# LEDMiniCube_Main.net
KiCad netlist of a schematic drawn in Altium Designer
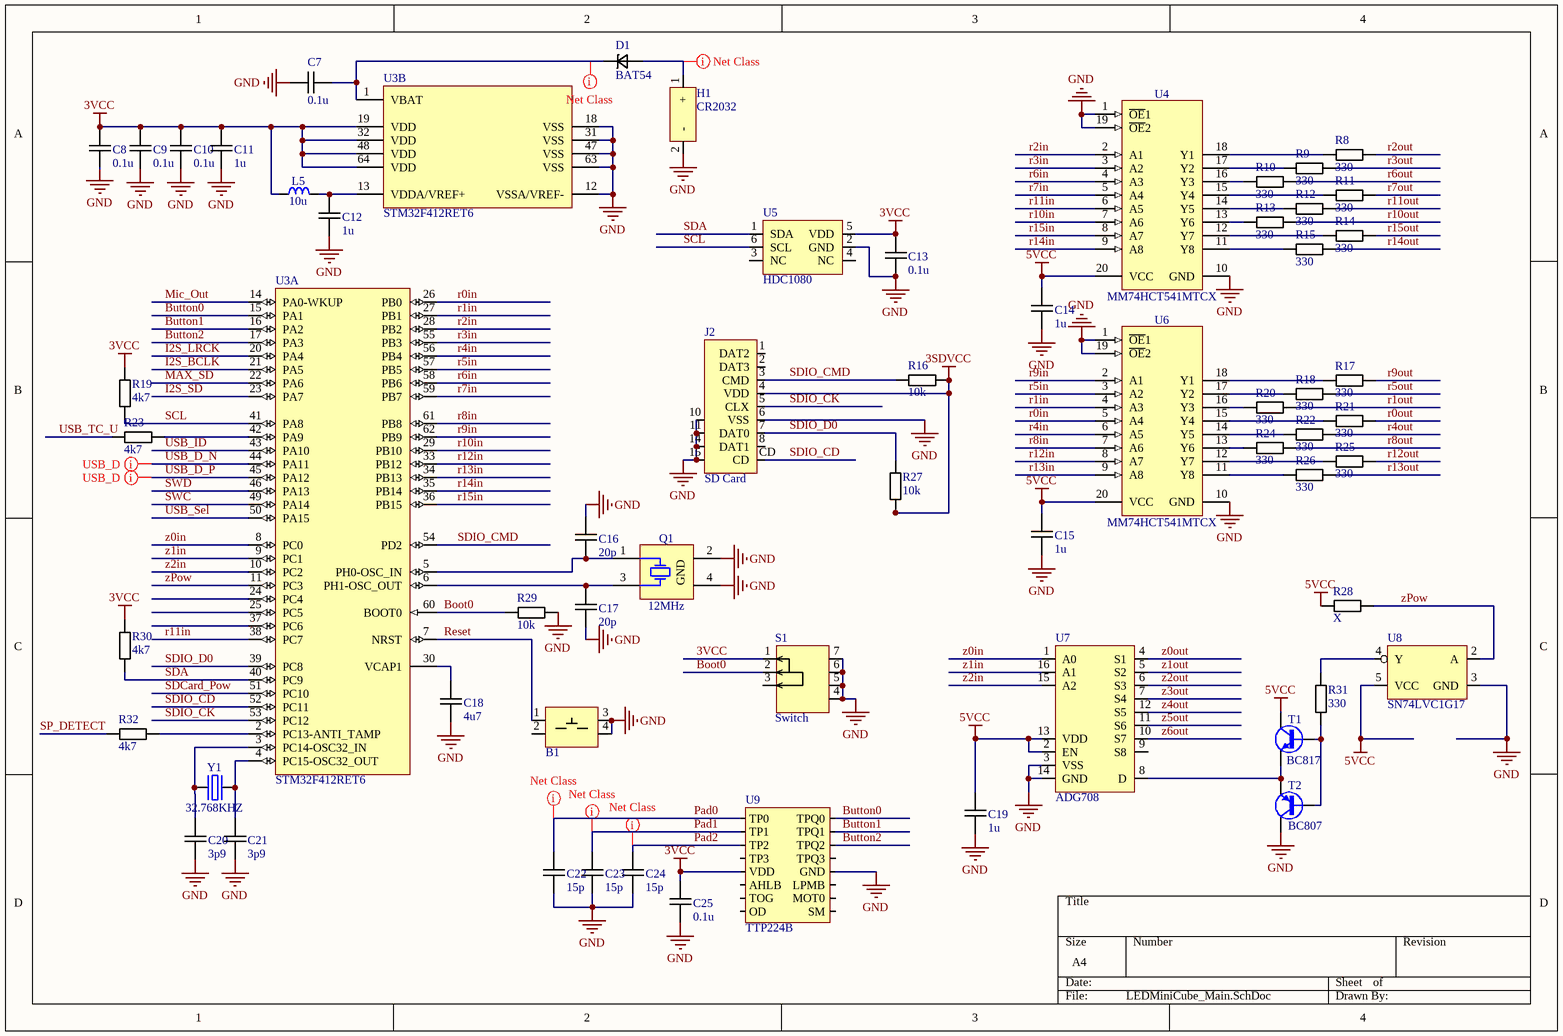
[diagram p0: LEDMiniCube_Main.SchDoc]

(export (version "E")
  (design (tool "Eeschema 10.0.6"))
  (components
    (comp (ref "B1")
      (value "Button 5.2")
      (footprint "Button 5.2x5.2")
      (libsource (lib "BMFT_lib") (part "Button 5.2"))
    )
    (comp (ref "C7") (value "0.1u") (footprint "CAPC1608L") (libsource (lib "BMFT_lib") (part "Capacitor")))
    (comp (ref "C8") (value "0.1u") (footprint "CAPC1608L") (libsource (lib "BMFT_lib") (part "Capacitor")))
    (comp (ref "C9") (value "0.1u") (footprint "CAPC1608L") (libsource (lib "BMFT_lib") (part "Capacitor")))
    (comp (ref "C10") (value "0.1u") (footprint "CAPC1608L") (libsource (lib "BMFT_lib") (part "Capacitor")))
    (comp (ref "C11") (value "1u") (footprint "CAPC1608L") (libsource (lib "BMFT_lib") (part "Capacitor")))
    (comp (ref "C12") (value "1u") (footprint "CAPC1608L") (libsource (lib "BMFT_lib") (part "Capacitor")))
    (comp (ref "C13") (value "0.1u") (footprint "CAPC1608L") (libsource (lib "BMFT_lib") (part "Capacitor")))
    (comp (ref "C14") (value "1u") (footprint "CAPC2012L") (libsource (lib "BMFT_lib") (part "Capacitor")))
    (comp (ref "C15") (value "1u") (footprint "CAPC2012L") (libsource (lib "BMFT_lib") (part "Capacitor")))
    (comp (ref "C16") (value "20p") (footprint "CAPC1608L") (libsource (lib "BMFT_lib") (part "Capacitor")))
    (comp (ref "C17") (value "20p") (footprint "CAPC1608L") (libsource (lib "BMFT_lib") (part "Capacitor")))
    (comp (ref "C18") (value "4u7") (footprint "CAPC2012L") (libsource (lib "BMFT_lib") (part "Capacitor")))
    (comp (ref "C19") (value "1u") (footprint "CAPC2012L") (libsource (lib "BMFT_lib") (part "Capacitor")))
    (comp (ref "C20") (value "3p9") (footprint "CAPC1608L") (libsource (lib "BMFT_lib") (part "Capacitor")))
    (comp (ref "C21") (value "3p9") (footprint "CAPC1608L") (libsource (lib "BMFT_lib") (part "Capacitor")))
    (comp (ref "C22") (value "15p") (footprint "CAPC1608L") (libsource (lib "BMFT_lib") (part "Capacitor")))
    (comp (ref "C23") (value "15p") (footprint "CAPC1608L") (libsource (lib "BMFT_lib") (part "Capacitor")))
    (comp (ref "C24") (value "15p") (footprint "CAPC1608L") (libsource (lib "BMFT_lib") (part "Capacitor")))
    (comp (ref "C25") (value "0.1u") (footprint "CAPC1608L") (libsource (lib "BMFT_lib") (part "Capacitor")))
    (comp (ref "D1") (value "BAT54") (footprint "SOD-323F") (libsource (lib "BMFT_lib") (part "Schotky")))
    (comp (ref "H1")
      (value "CR2032")
      (footprint "Battery Holder cr2032")
      (libsource (lib "BMFT_lib") (part "CR2032"))
    )
    (comp (ref "J2")
      (value "SD Card")
      (footprint "XUNPU TF-115")
      (libsource (lib "BMFT_lib") (part "SD Card Socket"))
    )
    (comp (ref "L5")
      (value "10u")
      (footprint "IND_ABRACON_AISC-0603")
      (description "Inductor")
      (fields (field (name "AUTHOR") "CERN DEM JLC"))
      (libsource (lib "Inductors & Transformers") (part "Inductor"))
    )
    (comp (ref "Q1")
      (value "12MHz")
      (footprint "XTAL_TXC_7M")
      (description "Crystal 4 pins 1=XTAL Control 2=GND3=XTAL 4=GND")
      (fields
        (field (name "PART NUMBER") "XTAL_12MHZ_TXC_7M-12.000MAAJ-T")
        (field (name "MANUFACTURER") "TXC CORPORATION")
        (field (name "AUTHOR") "CERN DEM JLC")
      )
      (libsource (lib "ICs And Semiconductors") (part "Quartz Crystal 1X 2GND 3X 4GND"))
    )
    (comp (ref "R8") (value "330") (footprint "RESC2012L") (libsource (lib "BMFT_lib") (part "Resistor")))
    (comp (ref "R9") (value "330") (footprint "RESC2012L") (libsource (lib "BMFT_lib") (part "Resistor")))
    (comp (ref "R10") (value "330") (footprint "RESC2012L") (libsource (lib "BMFT_lib") (part "Resistor")))
    (comp (ref "R11") (value "330") (footprint "RESC2012L") (libsource (lib "BMFT_lib") (part "Resistor")))
    (comp (ref "R12") (value "330") (footprint "RESC2012L") (libsource (lib "BMFT_lib") (part "Resistor")))
    (comp (ref "R13") (value "330") (footprint "RESC2012L") (libsource (lib "BMFT_lib") (part "Resistor")))
    (comp (ref "R14") (value "330") (footprint "RESC2012L") (libsource (lib "BMFT_lib") (part "Resistor")))
    (comp (ref "R15") (value "330") (footprint "RESC2012L") (libsource (lib "BMFT_lib") (part "Resistor")))
    (comp (ref "R16") (value "10k") (footprint "RESC1608L") (libsource (lib "BMFT_lib") (part "Resistor")))
    (comp (ref "R17") (value "330") (footprint "RESC2012L") (libsource (lib "BMFT_lib") (part "Resistor")))
    (comp (ref "R18") (value "330") (footprint "RESC2012L") (libsource (lib "BMFT_lib") (part "Resistor")))
    (comp (ref "R19") (value "4k7") (footprint "RESC1608L") (libsource (lib "BMFT_lib") (part "Resistor")))
    (comp (ref "R20") (value "330") (footprint "RESC2012L") (libsource (lib "BMFT_lib") (part "Resistor")))
    (comp (ref "R21") (value "330") (footprint "RESC2012L") (libsource (lib "BMFT_lib") (part "Resistor")))
    (comp (ref "R22") (value "330") (footprint "RESC2012L") (libsource (lib "BMFT_lib") (part "Resistor")))
    (comp (ref "R23") (value "4k7") (footprint "RESC1608L") (libsource (lib "BMFT_lib") (part "Resistor")))
    (comp (ref "R24") (value "330") (footprint "RESC2012L") (libsource (lib "BMFT_lib") (part "Resistor")))
    (comp (ref "R25") (value "330") (footprint "RESC2012L") (libsource (lib "BMFT_lib") (part "Resistor")))
    (comp (ref "R26") (value "330") (footprint "RESC2012L") (libsource (lib "BMFT_lib") (part "Resistor")))
    (comp (ref "R27") (value "10k") (footprint "RESC1608L") (libsource (lib "BMFT_lib") (part "Resistor")))
    (comp (ref "R28") (value "X") (footprint "RESC1608L") (libsource (lib "BMFT_lib") (part "Resistor")))
    (comp (ref "R29") (value "10k") (footprint "RESC1608L") (libsource (lib "BMFT_lib") (part "Resistor")))
    (comp (ref "R30") (value "4k7") (footprint "RESC1608L") (libsource (lib "BMFT_lib") (part "Resistor")))
    (comp (ref "R31") (value "330") (footprint "RESC1608L") (libsource (lib "BMFT_lib") (part "Resistor")))
    (comp (ref "R32") (value "4k7") (footprint "RESC1608L") (libsource (lib "BMFT_lib") (part "Resistor")))
    (comp (ref "S1") (value "Switch") (footprint "TA-3524A-A1") (libsource (lib "BMFT_lib") (part "Switch")))
    (comp (ref "T1")
      (value "BC817")
      (footprint "SOT95P230X110-3N")
      (description "NPN Transistor")
      (fields (field (name "PART NUMBER") "BC817-40") (field (name "AUTHOR") "CERN DEM JLC"))
      (libsource (lib "ICs And Semiconductors") (part "NPN B1 E2 C3"))
    )
    (comp (ref "T2")
      (value "BC807")
      (footprint "SOT95P230X110-3N")
      (description "PNP Transistor")
      (fields (field (name "PART NUMBER") "BC807-40") (field (name "AUTHOR") "CERN DEM JLC"))
      (libsource (lib "ICs And Semiconductors") (part "PNP B1 E2 C3"))
    )
    (comp (ref "U3")
      (value "STM32F412RET6")
      (footprint "STM-LQFP64_N")
      (libsource (lib "STMicroelectronics STM32 F4") (part "STM32F401RBT6"))
    )
    (comp (ref "U4")
      (value "MM74HCT541MTCX")
      (footprint "TSOP65P640X120-20N")
      (description "Octal Buffer/Line Driver with 3-State Outputs")
      (libsource (lib "Standard Logic") (part "74541"))
    )
    (comp (ref "U5")
      (value "HDC1080")
      (footprint "WSON HDC1080")
      (libsource (lib "BMFT_lib") (part "HDC1080"))
    )
    (comp (ref "U6")
      (value "MM74HCT541MTCX")
      (footprint "TSOP65P640X120-20N")
      (description "Octal Buffer/Line Driver with 3-State Outputs")
      (libsource (lib "Standard Logic") (part "74541"))
    )
    (comp (ref "U7")
      (value "ADG708")
      (footprint "TSOP65P640X110-16N")
      (fields (field (name "PART") "ADG708BRUZ"))
      (libsource (lib "BMFT_lib") (part "ADG708"))
    )
    (comp (ref "U8")
      (value "SN74LVC1G17")
      (footprint "SOT23-5AL")
      (fields (field (name "PART") "SN74LVC1G17DBVR"))
      (libsource (lib "BMFT_lib") (part "SN74LVC1G04"))
    )
    (comp (ref "U9")
      (value "TTP224B")
      (footprint "SOP65P640-16L")
      (libsource (lib "BMFT_lib") (part "TTP224"))
    )
    (comp (ref "Y1")
      (value "32.768KHZ")
      (footprint "XTAL_ABRACON_ABS09")
      (description "Quartz Crystal")
      (fields
        (field (name "PART NUMBER") "XTAL_32.768KHZ_ABRACON_ABS09-32.768KHZ-T")
        (field (name "MANUFACTURER") "ABRACON")
        (field (name "AUTHOR") "CERN DEM JLC")
      )
      (libsource (lib "ICs And Semiconductors") (part "Quartz Crystal"))
    )
  )
  (nets
    (net (code "1") (name "/Boot0") (class "Default")
      (node (ref "R29") (pin "1") (pintype "passive"))
      (node (ref "S1") (pin "2") (pinfunction "2_2") (pintype "passive"))
      (node (ref "U3") (pin "60") (pinfunction "BOOT0_60") (pintype "input"))
    )
    (net (code "2") (name "/Button0") (class "Default")
      (node (ref "U3") (pin "15") (pinfunction "PA1_15") (pintype "bidirectional"))
      (node (ref "U9") (pin "16") (pinfunction "TPQ0_16") (pintype "passive"))
    )
    (net (code "3") (name "/Button1") (class "Default")
      (node (ref "U3") (pin "16") (pinfunction "PA2_16") (pintype "bidirectional"))
      (node (ref "U9") (pin "15") (pinfunction "TPQ1_15") (pintype "passive"))
    )
    (net (code "4") (name "/Button2") (class "Default")
      (node (ref "U3") (pin "17") (pinfunction "PA3_17") (pintype "bidirectional"))
      (node (ref "U9") (pin "14") (pinfunction "TPQ2_14") (pintype "passive"))
    )
    (net (code "5") (name "/I2S_BCLK") (class "Default")
      (node (ref "U3") (pin "21") (pinfunction "PA5_21") (pintype "bidirectional"))
    )
    (net (code "6") (name "/I2S_LRCK") (class "Default")
      (node (ref "U3") (pin "20") (pinfunction "PA4_20") (pintype "bidirectional"))
    )
    (net (code "7") (name "/I2S_SD") (class "Default")
      (node (ref "U3") (pin "23") (pinfunction "PA7_23") (pintype "bidirectional"))
    )
    (net (code "8") (name "/MAX_SD") (class "Default")
      (node (ref "U3") (pin "22") (pinfunction "PA6_22") (pintype "bidirectional"))
    )
    (net (code "9") (name "/Mic_Out") (class "Default")
      (node (ref "U3") (pin "14") (pinfunction "PA0-WKUP_14") (pintype "bidirectional"))
    )
    (net (code "10") (name "/Pad0") (class "Default")
      (node (ref "C22") (pin "2") (pintype "passive"))
      (node (ref "U9") (pin "1") (pinfunction "TP0_1") (pintype "passive"))
    )
    (net (code "11") (name "/Pad1") (class "Default")
      (node (ref "C23") (pin "2") (pintype "passive"))
      (node (ref "U9") (pin "2") (pinfunction "TP1_2") (pintype "passive"))
    )
    (net (code "12") (name "/Pad2") (class "Default")
      (node (ref "C24") (pin "2") (pintype "passive"))
      (node (ref "U9") (pin "3") (pinfunction "TP2_3") (pintype "passive"))
    )
    (net (code "13") (name "/Reset") (class "Default")
      (node (ref "B1") (pin "1") (pinfunction "1_1") (pintype "passive"))
      (node (ref "U3") (pin "7") (pinfunction "NRST_7") (pintype "bidirectional"))
    )
    (net (code "14") (name "/SCL") (class "Default")
      (node (ref "R19") (pin "1") (pintype "passive"))
      (node (ref "U3") (pin "41") (pinfunction "PA8_41") (pintype "bidirectional"))
      (node (ref "U5") (pin "6") (pinfunction "SCL_6") (pintype "passive"))
    )
    (net (code "15") (name "/SDA") (class "Default")
      (node (ref "R30") (pin "1") (pintype "passive"))
      (node (ref "U3") (pin "40") (pinfunction "PC9_40") (pintype "bidirectional"))
      (node (ref "U5") (pin "1") (pinfunction "SDA_1") (pintype "passive"))
    )
    (net (code "16") (name "/SDCard_Pow") (class "Default")
      (node (ref "U3") (pin "51") (pinfunction "PC10_51") (pintype "bidirectional"))
    )
    (net (code "17") (name "/SDIO_CD") (class "Default")
      (node (ref "J2") (pin "CD") (pinfunction "CD_CD") (pintype "passive"))
      (node (ref "U3") (pin "52") (pinfunction "PC11_52") (pintype "bidirectional"))
    )
    (net (code "18") (name "/SDIO_CK") (class "Default")
      (node (ref "J2") (pin "5") (pinfunction "CLX_5") (pintype "passive"))
      (node (ref "U3") (pin "53") (pinfunction "PC12_53") (pintype "bidirectional"))
    )
    (net (code "19") (name "/SDIO_CMD") (class "Default")
      (node (ref "J2") (pin "3") (pinfunction "CMD_3") (pintype "passive"))
      (node (ref "R16") (pin "1") (pintype "passive"))
      (node (ref "U3") (pin "54") (pinfunction "PD2_54") (pintype "bidirectional"))
    )
    (net (code "20") (name "/SDIO_D0") (class "Default")
      (node (ref "J2") (pin "7") (pinfunction "DAT0_7") (pintype "passive"))
      (node (ref "R27") (pin "2") (pintype "passive"))
      (node (ref "U3") (pin "39") (pinfunction "PC8_39") (pintype "bidirectional"))
    )
    (net (code "21") (name "/SP_DETECT") (class "Default") (node (ref "R32") (pin "1") (pintype "passive")))
    (net (code "22") (name "/SWC") (class "Default")
      (node (ref "U3") (pin "49") (pinfunction "PA14_49") (pintype "bidirectional"))
    )
    (net (code "23") (name "/SWD") (class "Default")
      (node (ref "U3") (pin "46") (pinfunction "PA13_46") (pintype "bidirectional"))
    )
    (net (code "24") (name "/USB_D_N") (class "Default")
      (node (ref "U3") (pin "44") (pinfunction "PA11_44") (pintype "bidirectional"))
    )
    (net (code "25") (name "/USB_D_P") (class "Default")
      (node (ref "U3") (pin "45") (pinfunction "PA12_45") (pintype "bidirectional"))
    )
    (net (code "26") (name "/USB_ID") (class "Default")
      (node (ref "U3") (pin "43") (pinfunction "PA10_43") (pintype "bidirectional"))
    )
    (net (code "27") (name "/USB_Sel") (class "Default")
      (node (ref "U3") (pin "50") (pinfunction "PA15_50") (pintype "bidirectional"))
    )
    (net (code "28") (name "/USB_TC_U") (class "Default") (node (ref "R23") (pin "1") (pintype "passive")))
    (net (code "29") (name "/r0in") (class "Default")
      (node (ref "U3") (pin "26") (pinfunction "PB0_26") (pintype "bidirectional"))
      (node (ref "U6") (pin "5") (pinfunction "A4_5") (pintype "input"))
    )
    (net (code "30") (name "/r0out") (class "Default") (node (ref "R21") (pin "2") (pintype "passive")))
    (net (code "31") (name "/r1in") (class "Default")
      (node (ref "U3") (pin "27") (pinfunction "PB1_27") (pintype "bidirectional"))
      (node (ref "U6") (pin "4") (pinfunction "A3_4") (pintype "input"))
    )
    (net (code "32") (name "/r1out") (class "Default") (node (ref "R20") (pin "2") (pintype "passive")))
    (net (code "33") (name "/r2in") (class "Default")
      (node (ref "U3") (pin "28") (pinfunction "PB2_28") (pintype "bidirectional"))
      (node (ref "U4") (pin "2") (pinfunction "A1_2") (pintype "input"))
    )
    (net (code "34") (name "/r2out") (class "Default") (node (ref "R8") (pin "2") (pintype "passive")))
    (net (code "35") (name "/r3in") (class "Default")
      (node (ref "U3") (pin "55") (pinfunction "PB3_55") (pintype "bidirectional"))
      (node (ref "U4") (pin "3") (pinfunction "A2_3") (pintype "input"))
    )
    (net (code "36") (name "/r3out") (class "Default") (node (ref "R9") (pin "2") (pintype "passive")))
    (net (code "37") (name "/r4in") (class "Default")
      (node (ref "U3") (pin "56") (pinfunction "PB4_56") (pintype "bidirectional"))
      (node (ref "U6") (pin "6") (pinfunction "A5_6") (pintype "input"))
    )
    (net (code "38") (name "/r4out") (class "Default") (node (ref "R22") (pin "2") (pintype "passive")))
    (net (code "39") (name "/r5in") (class "Default")
      (node (ref "U3") (pin "57") (pinfunction "PB5_57") (pintype "bidirectional"))
      (node (ref "U6") (pin "3") (pinfunction "A2_3") (pintype "input"))
    )
    (net (code "40") (name "/r5out") (class "Default") (node (ref "R18") (pin "2") (pintype "passive")))
    (net (code "41") (name "/r6in") (class "Default")
      (node (ref "U3") (pin "58") (pinfunction "PB6_58") (pintype "bidirectional"))
      (node (ref "U4") (pin "4") (pinfunction "A3_4") (pintype "input"))
    )
    (net (code "42") (name "/r6out") (class "Default") (node (ref "R10") (pin "2") (pintype "passive")))
    (net (code "43") (name "/r7in") (class "Default")
      (node (ref "U3") (pin "59") (pinfunction "PB7_59") (pintype "bidirectional"))
      (node (ref "U4") (pin "5") (pinfunction "A4_5") (pintype "input"))
    )
    (net (code "44") (name "/r7out") (class "Default") (node (ref "R11") (pin "2") (pintype "passive")))
    (net (code "45") (name "/r8in") (class "Default")
      (node (ref "U3") (pin "61") (pinfunction "PB8_61") (pintype "bidirectional"))
      (node (ref "U6") (pin "7") (pinfunction "A6_7") (pintype "input"))
    )
    (net (code "46") (name "/r8out") (class "Default") (node (ref "R24") (pin "2") (pintype "passive")))
    (net (code "47") (name "/r9in") (class "Default")
      (node (ref "U3") (pin "62") (pinfunction "PB9_62") (pintype "bidirectional"))
      (node (ref "U6") (pin "2") (pinfunction "A1_2") (pintype "input"))
    )
    (net (code "48") (name "/r9out") (class "Default") (node (ref "R17") (pin "2") (pintype "passive")))
    (net (code "49") (name "/r10in") (class "Default")
      (node (ref "U3") (pin "29") (pinfunction "PB10_29") (pintype "bidirectional"))
      (node (ref "U4") (pin "7") (pinfunction "A6_7") (pintype "input"))
    )
    (net (code "50") (name "/r10out") (class "Default") (node (ref "R13") (pin "2") (pintype "passive")))
    (net (code "51") (name "/r11in") (class "Default")
      (node (ref "U3") (pin "38") (pinfunction "PC7_38") (pintype "bidirectional"))
      (node (ref "U4") (pin "6") (pinfunction "A5_6") (pintype "input"))
    )
    (net (code "52") (name "/r11out") (class "Default") (node (ref "R12") (pin "2") (pintype "passive")))
    (net (code "53") (name "/r12in") (class "Default")
      (node (ref "U3") (pin "33") (pinfunction "PB12_33") (pintype "bidirectional"))
      (node (ref "U6") (pin "8") (pinfunction "A7_8") (pintype "input"))
    )
    (net (code "54") (name "/r12out") (class "Default") (node (ref "R25") (pin "2") (pintype "passive")))
    (net (code "55") (name "/r13in") (class "Default")
      (node (ref "U3") (pin "34") (pinfunction "PB13_34") (pintype "bidirectional"))
      (node (ref "U6") (pin "9") (pinfunction "A8_9") (pintype "input"))
    )
    (net (code "56") (name "/r13out") (class "Default") (node (ref "R26") (pin "2") (pintype "passive")))
    (net (code "57") (name "/r14in") (class "Default")
      (node (ref "U3") (pin "35") (pinfunction "PB14_35") (pintype "bidirectional"))
      (node (ref "U4") (pin "9") (pinfunction "A8_9") (pintype "input"))
    )
    (net (code "58") (name "/r14out") (class "Default") (node (ref "R15") (pin "2") (pintype "passive")))
    (net (code "59") (name "/r15in") (class "Default")
      (node (ref "U3") (pin "36") (pinfunction "PB15_36") (pintype "bidirectional"))
      (node (ref "U4") (pin "8") (pinfunction "A7_8") (pintype "input"))
    )
    (net (code "60") (name "/r15out") (class "Default") (node (ref "R14") (pin "2") (pintype "passive")))
    (net (code "61") (name "/z0in") (class "Default")
      (node (ref "U3") (pin "8") (pinfunction "PC0_8") (pintype "bidirectional"))
      (node (ref "U7") (pin "1") (pinfunction "A0_1") (pintype "passive"))
    )
    (net (code "62") (name "/z0out") (class "Default")
      (node (ref "U7") (pin "4") (pinfunction "S1_4") (pintype "passive"))
    )
    (net (code "63") (name "/z1in") (class "Default")
      (node (ref "U3") (pin "9") (pinfunction "PC1_9") (pintype "bidirectional"))
      (node (ref "U7") (pin "16") (pinfunction "A1_16") (pintype "passive"))
    )
    (net (code "64") (name "/z1out") (class "Default")
      (node (ref "U7") (pin "5") (pinfunction "S2_5") (pintype "passive"))
    )
    (net (code "65") (name "/z2in") (class "Default")
      (node (ref "U3") (pin "10") (pinfunction "PC2_10") (pintype "bidirectional"))
      (node (ref "U7") (pin "15") (pinfunction "A2_15") (pintype "passive"))
    )
    (net (code "66") (name "/z2out") (class "Default")
      (node (ref "U7") (pin "6") (pinfunction "S3_6") (pintype "passive"))
    )
    (net (code "67") (name "/z3out") (class "Default")
      (node (ref "U7") (pin "7") (pinfunction "S4_7") (pintype "passive"))
    )
    (net (code "68") (name "/z4out") (class "Default")
      (node (ref "U7") (pin "12") (pinfunction "S5_12") (pintype "passive"))
    )
    (net (code "69") (name "/z5out") (class "Default")
      (node (ref "U7") (pin "11") (pinfunction "S6_11") (pintype "passive"))
    )
    (net (code "70") (name "/z6out") (class "Default")
      (node (ref "U7") (pin "10") (pinfunction "S7_10") (pintype "passive"))
    )
    (net (code "71") (name "/zPow") (class "Default")
      (node (ref "R28") (pin "1") (pintype "passive"))
      (node (ref "U3") (pin "11") (pinfunction "PC3_11") (pintype "bidirectional"))
      (node (ref "U8") (pin "2") (pinfunction "A_2") (pintype "passive"))
    )
    (net (code "72") (name "3SDVCC") (class "Default")
      (node (ref "J2") (pin "4") (pinfunction "VDD_4") (pintype "passive"))
      (node (ref "R16") (pin "2") (pintype "passive"))
      (node (ref "R27") (pin "1") (pintype "passive"))
    )
    (net (code "73") (name "3VCC") (class "Default")
      (node (ref "C10") (pin "2") (pintype "passive"))
      (node (ref "C11") (pin "2") (pintype "passive"))
      (node (ref "C13") (pin "2") (pintype "passive"))
      (node (ref "C25") (pin "2") (pintype "passive"))
      (node (ref "C8") (pin "2") (pintype "passive"))
      (node (ref "C9") (pin "2") (pintype "passive"))
      (node (ref "L5") (pin "1") (pinfunction "1_1") (pintype "passive"))
      (node (ref "R19") (pin "2") (pintype "passive"))
      (node (ref "R30") (pin "2") (pintype "passive"))
      (node (ref "S1") (pin "1") (pinfunction "1_1") (pintype "passive"))
      (node (ref "U3") (pin "19") (pinfunction "VDD_19") (pintype "power_in"))
      (node (ref "U3") (pin "32") (pinfunction "VDD_32") (pintype "power_in"))
      (node (ref "U3") (pin "48") (pinfunction "VDD_48") (pintype "power_in"))
      (node (ref "U3") (pin "64") (pinfunction "VDD_64") (pintype "power_in"))
      (node (ref "U5") (pin "5") (pinfunction "VDD_5") (pintype "passive"))
      (node (ref "U9") (pin "6") (pinfunction "VDD_6") (pintype "passive"))
    )
    (net (code "74") (name "5VCC") (class "Default")
      (node (ref "C14") (pin "2") (pintype "passive"))
      (node (ref "C15") (pin "2") (pintype "passive"))
      (node (ref "C19") (pin "2") (pintype "passive"))
      (node (ref "R28") (pin "2") (pintype "passive"))
      (node (ref "T1") (pin "3") (pinfunction "C_3") (pintype "passive"))
      (node (ref "U4") (pin "20") (pinfunction "VCC_20") (pintype "power_in"))
      (node (ref "U6") (pin "20") (pinfunction "VCC_20") (pintype "power_in"))
      (node (ref "U7") (pin "13") (pinfunction "VDD_13") (pintype "passive"))
      (node (ref "U7") (pin "2") (pinfunction "EN_2") (pintype "passive"))
      (node (ref "U8") (pin "5") (pinfunction "VCC_5") (pintype "passive"))
    )
    (net (code "75") (name "GND") (class "Default")
      (node (ref "B1") (pin "3") (pinfunction "3_3") (pintype "passive"))
      (node (ref "B1") (pin "4") (pinfunction "4_4") (pintype "passive"))
      (node (ref "C10") (pin "1") (pintype "passive"))
      (node (ref "C11") (pin "1") (pintype "passive"))
      (node (ref "C12") (pin "1") (pintype "passive"))
      (node (ref "C13") (pin "1") (pintype "passive"))
      (node (ref "C14") (pin "1") (pintype "passive"))
      (node (ref "C15") (pin "1") (pintype "passive"))
      (node (ref "C16") (pin "2") (pintype "passive"))
      (node (ref "C17") (pin "1") (pintype "passive"))
      (node (ref "C18") (pin "1") (pintype "passive"))
      (node (ref "C19") (pin "1") (pintype "passive"))
      (node (ref "C20") (pin "1") (pintype "passive"))
      (node (ref "C21") (pin "1") (pintype "passive"))
      (node (ref "C22") (pin "1") (pintype "passive"))
      (node (ref "C23") (pin "1") (pintype "passive"))
      (node (ref "C24") (pin "1") (pintype "passive"))
      (node (ref "C25") (pin "1") (pintype "passive"))
      (node (ref "C7") (pin "2") (pintype "passive"))
      (node (ref "C8") (pin "1") (pintype "passive"))
      (node (ref "C9") (pin "1") (pintype "passive"))
      (node (ref "H1") (pin "2") (pinfunction "-_2") (pintype "passive"))
      (node (ref "J2") (pin "10") (pintype "passive"))
      (node (ref "J2") (pin "11") (pintype "passive"))
      (node (ref "J2") (pin "14") (pintype "passive"))
      (node (ref "J2") (pin "15") (pintype "passive"))
      (node (ref "J2") (pin "6") (pinfunction "VSS_6") (pintype "passive"))
      (node (ref "Q1") (pin "2") (pinfunction "GND_2") (pintype "power_in"))
      (node (ref "Q1") (pin "4") (pinfunction "GND_4") (pintype "power_in"))
      (node (ref "R29") (pin "2") (pintype "passive"))
      (node (ref "S1") (pin "4") (pinfunction "4_4") (pintype "passive"))
      (node (ref "S1") (pin "5") (pinfunction "5_5") (pintype "passive"))
      (node (ref "S1") (pin "6") (pinfunction "6_6") (pintype "passive"))
      (node (ref "S1") (pin "7") (pinfunction "7_7") (pintype "passive"))
      (node (ref "T2") (pin "3") (pinfunction "C_3") (pintype "passive"))
      (node (ref "U3") (pin "12") (pinfunction "VSSA/VREF-_12") (pintype "power_in"))
      (node (ref "U3") (pin "18") (pinfunction "VSS_18") (pintype "power_in"))
      (node (ref "U3") (pin "31") (pinfunction "VSS_31") (pintype "power_in"))
      (node (ref "U3") (pin "47") (pinfunction "VSS_47") (pintype "power_in"))
      (node (ref "U3") (pin "63") (pinfunction "VSS_63") (pintype "power_in"))
      (node (ref "U4") (pin "1") (pinfunction "~{OE}1_1") (pintype "input"))
      (node (ref "U4") (pin "10") (pinfunction "GND_10") (pintype "power_in"))
      (node (ref "U4") (pin "19") (pinfunction "~{OE}2_19") (pintype "input"))
      (node (ref "U5") (pin "2") (pinfunction "GND_2") (pintype "passive"))
      (node (ref "U6") (pin "1") (pinfunction "~{OE}1_1") (pintype "input"))
      (node (ref "U6") (pin "10") (pinfunction "GND_10") (pintype "power_in"))
      (node (ref "U6") (pin "19") (pinfunction "~{OE}2_19") (pintype "input"))
      (node (ref "U7") (pin "14") (pinfunction "GND_14") (pintype "passive"))
      (node (ref "U7") (pin "3") (pinfunction "VSS_3") (pintype "passive"))
      (node (ref "U8") (pin "3") (pinfunction "GND_3") (pintype "passive"))
      (node (ref "U9") (pin "10") (pinfunction "GND_10") (pintype "passive"))
    )
    (net (code "76") (name "Net-(H1-+)") (class "Default")
      (node (ref "D1") (pin "1") (pintype "passive"))
      (node (ref "H1") (pin "1") (pinfunction "+_1") (pintype "passive"))
    )
    (net (code "77") (name "Net-(T1-B)") (class "Default")
      (node (ref "R31") (pin "1") (pintype "passive"))
      (node (ref "T1") (pin "1") (pinfunction "B_1") (pintype "passive"))
      (node (ref "T2") (pin "1") (pinfunction "B_1") (pintype "passive"))
    )
    (net (code "78") (name "Net-(T1-E)") (class "Default")
      (node (ref "T1") (pin "2") (pinfunction "E_2") (pintype "passive"))
      (node (ref "T2") (pin "2") (pinfunction "E_2") (pintype "passive"))
      (node (ref "U7") (pin "8") (pinfunction "D_8") (pintype "passive"))
    )
    (net (code "79") (name "Net-(U3A-PA9)") (class "Default")
      (node (ref "R23") (pin "2") (pintype "passive"))
      (node (ref "U3") (pin "42") (pinfunction "PA9_42") (pintype "bidirectional"))
    )
    (net (code "80") (name "Net-(U3A-PC13-ANTI_TAMP)") (class "Default")
      (node (ref "R32") (pin "2") (pintype "passive"))
      (node (ref "U3") (pin "2") (pinfunction "PC13-ANTI_TAMP_2") (pintype "bidirectional"))
    )
    (net (code "81") (name "Net-(U3A-PC14-OSC32_IN)") (class "Default")
      (node (ref "C20") (pin "2") (pintype "passive"))
      (node (ref "U3") (pin "3") (pinfunction "PC14-OSC32_IN_3") (pintype "bidirectional"))
      (node (ref "Y1") (pin "1") (pinfunction "OSC1_1") (pintype "passive"))
    )
    (net (code "82") (name "Net-(U3A-PC15-OSC32_OUT)") (class "Default")
      (node (ref "C21") (pin "2") (pintype "passive"))
      (node (ref "U3") (pin "4") (pinfunction "PC15-OSC32_OUT_4") (pintype "bidirectional"))
      (node (ref "Y1") (pin "2") (pinfunction "OSC2_2") (pintype "passive"))
    )
    (net (code "83") (name "Net-(U3A-PH0-OSC_IN)") (class "Default")
      (node (ref "C16") (pin "1") (pintype "passive"))
      (node (ref "Q1") (pin "1") (pinfunction "X_1") (pintype "passive"))
      (node (ref "U3") (pin "5") (pinfunction "PH0-OSC_IN_5") (pintype "bidirectional"))
    )
    (net (code "84") (name "Net-(U3A-PH1-OSC_OUT)") (class "Default")
      (node (ref "C17") (pin "2") (pintype "passive"))
      (node (ref "Q1") (pin "3") (pinfunction "X_3") (pintype "passive"))
      (node (ref "U3") (pin "6") (pinfunction "PH1-OSC_OUT_6") (pintype "bidirectional"))
    )
    (net (code "85") (name "Net-(U3A-VCAP1)") (class "Default")
      (node (ref "C18") (pin "2") (pintype "passive"))
      (node (ref "U3") (pin "30") (pinfunction "VCAP1_30") (pintype "power_in"))
    )
    (net (code "86") (name "Net-(U3B-VBAT)") (class "Default")
      (node (ref "C7") (pin "1") (pintype "passive"))
      (node (ref "D1") (pin "2") (pintype "passive"))
      (node (ref "U3") (pin "1") (pinfunction "VBAT_1") (pintype "power_in"))
    )
    (net (code "87") (name "Net-(U3B-VDDA{slash}VREF+)") (class "Default")
      (node (ref "C12") (pin "2") (pintype "passive"))
      (node (ref "L5") (pin "2") (pinfunction "2_2") (pintype "passive"))
      (node (ref "U3") (pin "13") (pinfunction "VDDA/VREF+_13") (pintype "power_in"))
    )
    (net (code "88") (name "Net-(U4-Y1)") (class "Default")
      (node (ref "R8") (pin "1") (pintype "passive"))
      (node (ref "U4") (pin "18") (pinfunction "Y1_18") (pintype "tri_state"))
    )
    (net (code "89") (name "Net-(U4-Y2)") (class "Default")
      (node (ref "R9") (pin "1") (pintype "passive"))
      (node (ref "U4") (pin "17") (pinfunction "Y2_17") (pintype "tri_state"))
    )
    (net (code "90") (name "Net-(U4-Y3)") (class "Default")
      (node (ref "R10") (pin "1") (pintype "passive"))
      (node (ref "U4") (pin "16") (pinfunction "Y3_16") (pintype "tri_state"))
    )
    (net (code "91") (name "Net-(U4-Y4)") (class "Default")
      (node (ref "R11") (pin "1") (pintype "passive"))
      (node (ref "U4") (pin "15") (pinfunction "Y4_15") (pintype "tri_state"))
    )
    (net (code "92") (name "Net-(U4-Y5)") (class "Default")
      (node (ref "R12") (pin "1") (pintype "passive"))
      (node (ref "U4") (pin "14") (pinfunction "Y5_14") (pintype "tri_state"))
    )
    (net (code "93") (name "Net-(U4-Y6)") (class "Default")
      (node (ref "R13") (pin "1") (pintype "passive"))
      (node (ref "U4") (pin "13") (pinfunction "Y6_13") (pintype "tri_state"))
    )
    (net (code "94") (name "Net-(U4-Y7)") (class "Default")
      (node (ref "R14") (pin "1") (pintype "passive"))
      (node (ref "U4") (pin "12") (pinfunction "Y7_12") (pintype "tri_state"))
    )
    (net (code "95") (name "Net-(U4-Y8)") (class "Default")
      (node (ref "R15") (pin "1") (pintype "passive"))
      (node (ref "U4") (pin "11") (pinfunction "Y8_11") (pintype "tri_state"))
    )
    (net (code "96") (name "Net-(U6-Y1)") (class "Default")
      (node (ref "R17") (pin "1") (pintype "passive"))
      (node (ref "U6") (pin "18") (pinfunction "Y1_18") (pintype "tri_state"))
    )
    (net (code "97") (name "Net-(U6-Y2)") (class "Default")
      (node (ref "R18") (pin "1") (pintype "passive"))
      (node (ref "U6") (pin "17") (pinfunction "Y2_17") (pintype "tri_state"))
    )
    (net (code "98") (name "Net-(U6-Y3)") (class "Default")
      (node (ref "R20") (pin "1") (pintype "passive"))
      (node (ref "U6") (pin "16") (pinfunction "Y3_16") (pintype "tri_state"))
    )
    (net (code "99") (name "Net-(U6-Y4)") (class "Default")
      (node (ref "R21") (pin "1") (pintype "passive"))
      (node (ref "U6") (pin "15") (pinfunction "Y4_15") (pintype "tri_state"))
    )
    (net (code "100") (name "Net-(U6-Y5)") (class "Default")
      (node (ref "R22") (pin "1") (pintype "passive"))
      (node (ref "U6") (pin "14") (pinfunction "Y5_14") (pintype "tri_state"))
    )
    (net (code "101") (name "Net-(U6-Y6)") (class "Default")
      (node (ref "R24") (pin "1") (pintype "passive"))
      (node (ref "U6") (pin "13") (pinfunction "Y6_13") (pintype "tri_state"))
    )
    (net (code "102") (name "Net-(U6-Y7)") (class "Default")
      (node (ref "R25") (pin "1") (pintype "passive"))
      (node (ref "U6") (pin "12") (pinfunction "Y7_12") (pintype "tri_state"))
    )
    (net (code "103") (name "Net-(U6-Y8)") (class "Default")
      (node (ref "R26") (pin "1") (pintype "passive"))
      (node (ref "U6") (pin "11") (pinfunction "Y8_11") (pintype "tri_state"))
    )
    (net (code "104") (name "Net-(U8-Y)") (class "Default")
      (node (ref "R31") (pin "2") (pintype "passive"))
      (node (ref "U8") (pin "4") (pinfunction "Y_4") (pintype "passive"))
    )
    (net (code "105") (name "unconnected-(B1-Pad2)") (class "Default")
      (node (ref "B1") (pin "2") (pinfunction "2_2") (pintype "passive"))
    )
    (net (code "106") (name "unconnected-(J2-DAT1-Pad8)") (class "Default")
      (node (ref "J2") (pin "8") (pinfunction "DAT1_8") (pintype "passive"))
    )
    (net (code "107") (name "unconnected-(J2-DAT2-Pad1)") (class "Default")
      (node (ref "J2") (pin "1") (pinfunction "DAT2_1") (pintype "passive"))
    )
    (net (code "108") (name "unconnected-(J2-DAT3-Pad2)") (class "Default")
      (node (ref "J2") (pin "2") (pinfunction "DAT3_2") (pintype "passive"))
    )
    (net (code "109") (name "unconnected-(S1-Pad3)") (class "Default")
      (node (ref "S1") (pin "3") (pinfunction "3_3") (pintype "passive"))
    )
    (net (code "110") (name "unconnected-(U3A-PC4-Pad24)") (class "Default")
      (node (ref "U3") (pin "24") (pinfunction "PC4_24") (pintype "bidirectional"))
    )
    (net (code "111") (name "unconnected-(U3A-PC5-Pad25)") (class "Default")
      (node (ref "U3") (pin "25") (pinfunction "PC5_25") (pintype "bidirectional"))
    )
    (net (code "112") (name "unconnected-(U3A-PC6-Pad37)") (class "Default")
      (node (ref "U3") (pin "37") (pinfunction "PC6_37") (pintype "bidirectional"))
    )
    (net (code "113") (name "unconnected-(U5-NC-Pad3)") (class "Default")
      (node (ref "U5") (pin "3") (pinfunction "NC_3") (pintype "passive"))
    )
    (net (code "114") (name "unconnected-(U5-NC-Pad4)") (class "Default")
      (node (ref "U5") (pin "4") (pinfunction "NC_4") (pintype "passive"))
    )
    (net (code "115") (name "unconnected-(U7-S8-Pad9)") (class "Default")
      (node (ref "U7") (pin "9") (pinfunction "S8_9") (pintype "passive"))
    )
    (net (code "116") (name "unconnected-(U9-AHLB-Pad5)") (class "Default")
      (node (ref "U9") (pin "5") (pinfunction "AHLB_5") (pintype "passive"))
    )
    (net (code "117") (name "unconnected-(U9-LPMB-Pad8)") (class "Default")
      (node (ref "U9") (pin "8") (pinfunction "LPMB_8") (pintype "passive"))
    )
    (net (code "118") (name "unconnected-(U9-MOT0-Pad9)") (class "Default")
      (node (ref "U9") (pin "9") (pinfunction "MOT0_9") (pintype "passive"))
    )
    (net (code "119") (name "unconnected-(U9-OD-Pad11)") (class "Default")
      (node (ref "U9") (pin "11") (pinfunction "OD_11") (pintype "passive"))
    )
    (net (code "120") (name "unconnected-(U9-SM-Pad12)") (class "Default")
      (node (ref "U9") (pin "12") (pinfunction "SM_12") (pintype "passive"))
    )
    (net (code "121") (name "unconnected-(U9-TOG-Pad7)") (class "Default")
      (node (ref "U9") (pin "7") (pinfunction "TOG_7") (pintype "passive"))
    )
    (net (code "122") (name "unconnected-(U9-TP3-Pad4)") (class "Default")
      (node (ref "U9") (pin "4") (pinfunction "TP3_4") (pintype "passive"))
    )
    (net (code "123") (name "unconnected-(U9-TPQ3-Pad13)") (class "Default")
      (node (ref "U9") (pin "13") (pinfunction "TPQ3_13") (pintype "passive"))
    )
  )
)
